# PowCarbinBoard_Connect.net
KiCad netlist of a schematic drawn in Altium Designer
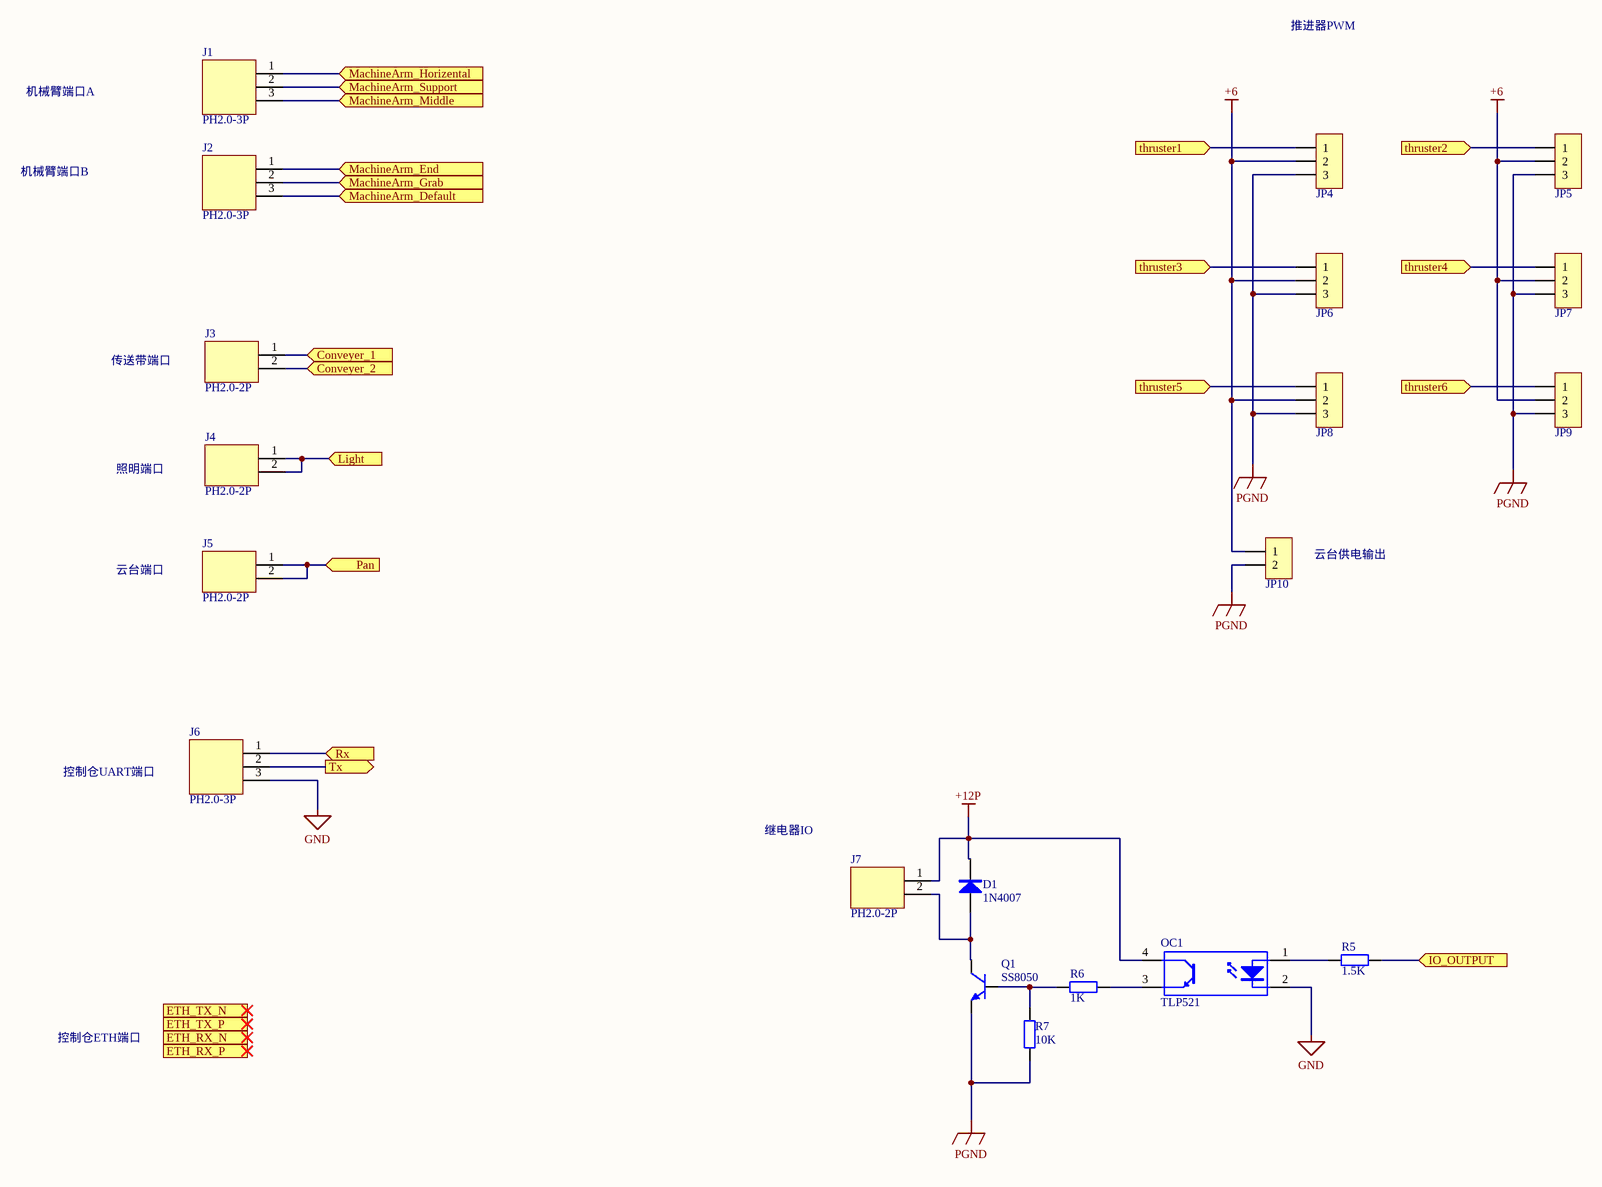
[diagram p0: PowCarbinBoard_Connect.SchDoc]

(export (version "E")
  (design (tool "Eeschema 10.0.6"))
  (components
    (comp (ref "D1")
      (value "1N4007")
      (footprint "SOD-123")
      (description "整流二极管")
      (fields (field (name "版权归属") "源创客"))
      (libsource (lib "8.1   - 二极管-整流桥") (part "1N4007"))
    )
    (comp (ref "J1") (value "PH2.0-3P") (footprint "PH2.0-3P") (libsource (lib "PH") (part "PH2.0-3P")))
    (comp (ref "J2") (value "PH2.0-3P") (footprint "PH2.0-3P") (libsource (lib "PH") (part "PH2.0-3P")))
    (comp (ref "J3") (value "PH2.0-2P") (footprint "PH2.0-2P") (libsource (lib "PH") (part "PH2.0-2P")))
    (comp (ref "J4") (value "PH2.0-2P") (footprint "PH2.0-2P") (libsource (lib "PH") (part "PH2.0-2P")))
    (comp (ref "J5") (value "PH2.0-2P") (footprint "PH2.0-2P") (libsource (lib "PH") (part "PH2.0-2P")))
    (comp (ref "J6") (value "PH2.0-3P") (footprint "PH2.0-3P") (libsource (lib "PH") (part "PH2.0-3P")))
    (comp (ref "J7") (value "PH2.0-2P") (footprint "PH2.0-2P") (libsource (lib "PH") (part "PH2.0-2P")))
    (comp (ref "JP4")
      (value "HDR-1X3")
      (footprint "HDR2.54-LI-3P")
      (description "3P接插件")
      (fields (field (name "版权归属") "源创客"))
      (libsource (lib "4.5   - 接插件-脚距2.54") (part "Header 3"))
    )
    (comp (ref "JP5")
      (value "HDR-1X3")
      (footprint "HDR2.54-LI-3P")
      (description "3P接插件")
      (fields (field (name "版权归属") "源创客"))
      (libsource (lib "4.5   - 接插件-脚距2.54") (part "Header 3"))
    )
    (comp (ref "JP6")
      (value "HDR-1X3")
      (footprint "HDR2.54-LI-3P")
      (description "3P接插件")
      (fields (field (name "版权归属") "源创客"))
      (libsource (lib "4.5   - 接插件-脚距2.54") (part "Header 3"))
    )
    (comp (ref "JP7")
      (value "HDR-1X3")
      (footprint "HDR2.54-LI-3P")
      (description "3P接插件")
      (fields (field (name "版权归属") "源创客"))
      (libsource (lib "4.5   - 接插件-脚距2.54") (part "Header 3"))
    )
    (comp (ref "JP8")
      (value "HDR-1X3")
      (footprint "HDR2.54-LI-3P")
      (description "3P接插件")
      (fields (field (name "版权归属") "源创客"))
      (libsource (lib "4.5   - 接插件-脚距2.54") (part "Header 3"))
    )
    (comp (ref "JP9")
      (value "HDR-1X3")
      (footprint "HDR2.54-LI-3P")
      (description "3P接插件")
      (fields (field (name "版权归属") "源创客"))
      (libsource (lib "4.5   - 接插件-脚距2.54") (part "Header 3"))
    )
    (comp (ref "JP10")
      (value "HDR-1X2")
      (footprint "KF128-5.08-2P")
      (description "2P接插件")
      (fields (field (name "版权归属") "源创客"))
      (libsource (lib "4.10 - 接插件-脚距5.08") (part "Header 2"))
    )
    (comp (ref "OC1")
      (value "TLP521")
      (footprint "DIP_TLP521")
      (description "开关光耦")
      (libsource (lib "光电隔离器") (part "TLP521"))
    )
    (comp (ref "Q1")
      (value "SS8050")
      (footprint "SOT23-3N")
      (description "高频放大-NPN型")
      (fields (field (name "版权归属") "源创客"))
      (libsource (lib "6.2   - 三极管") (part "8050-SMD"))
    )
    (comp (ref "R5")
      (value "1.5K")
      (footprint "0603_R")
      (description "贴片电阻")
      (libsource (lib "") (part "0603 10KΩ (1002) 1%_1"))
    )
    (comp (ref "R6")
      (value "1K")
      (footprint "0603_R")
      (description "贴片电阻")
      (libsource (lib "Miscellaneous Devices LC") (part "0603 10KΩ (1002) 1%"))
    )
    (comp (ref "R7")
      (value "10K")
      (footprint "0603_R")
      (description "贴片电阻")
      (libsource (lib "") (part "0603 10KΩ (1002) 1%_2"))
    )
  )
  (nets
    (net (code "1") (name "+6") (class "Default")
      (node (ref "JP10") (pin "1") (pinfunction "1_1") (pintype "passive"))
      (node (ref "JP4") (pin "2") (pinfunction "2_2") (pintype "passive"))
      (node (ref "JP5") (pin "2") (pinfunction "2_2") (pintype "passive"))
      (node (ref "JP6") (pin "2") (pinfunction "2_2") (pintype "passive"))
      (node (ref "JP7") (pin "2") (pinfunction "2_2") (pintype "passive"))
      (node (ref "JP8") (pin "2") (pinfunction "2_2") (pintype "passive"))
      (node (ref "JP9") (pin "2") (pinfunction "2_2") (pintype "passive"))
    )
    (net (code "2") (name "+12P") (class "Default")
      (node (ref "D1") (pin "2") (pinfunction "K_2") (pintype "passive"))
      (node (ref "J7") (pin "1") (pinfunction "1_1") (pintype "passive"))
      (node (ref "OC1") (pin "4") (pinfunction "C_4") (pintype "passive"))
    )
    (net (code "3") (name "/Conveyer_1") (class "Default")
      (node (ref "J3") (pin "1") (pinfunction "1_1") (pintype "passive"))
    )
    (net (code "4") (name "/Conveyer_2") (class "Default")
      (node (ref "J3") (pin "2") (pinfunction "2_2") (pintype "passive"))
    )
    (net (code "9") (name "/IO_OUTPUT") (class "Default")
      (node (ref "R5") (pin "2") (pinfunction "2_2") (pintype "passive"))
    )
    (net (code "10") (name "/Light") (class "Default")
      (node (ref "J4") (pin "1") (pinfunction "1_1") (pintype "passive"))
      (node (ref "J4") (pin "2") (pinfunction "2_2") (pintype "passive"))
    )
    (net (code "11") (name "/MachineArm_Default") (class "Default")
      (node (ref "J2") (pin "3") (pinfunction "3_3") (pintype "passive"))
    )
    (net (code "12") (name "/MachineArm_End") (class "Default")
      (node (ref "J2") (pin "1") (pinfunction "1_1") (pintype "passive"))
    )
    (net (code "13") (name "/MachineArm_Grab") (class "Default")
      (node (ref "J2") (pin "2") (pinfunction "2_2") (pintype "passive"))
    )
    (net (code "14") (name "/MachineArm_Horizental") (class "Default")
      (node (ref "J1") (pin "1") (pinfunction "1_1") (pintype "passive"))
    )
    (net (code "15") (name "/MachineArm_Middle") (class "Default")
      (node (ref "J1") (pin "3") (pinfunction "3_3") (pintype "passive"))
    )
    (net (code "16") (name "/MachineArm_Support") (class "Default")
      (node (ref "J1") (pin "2") (pinfunction "2_2") (pintype "passive"))
    )
    (net (code "17") (name "/Pan") (class "Default")
      (node (ref "J5") (pin "1") (pinfunction "1_1") (pintype "passive"))
      (node (ref "J5") (pin "2") (pinfunction "2_2") (pintype "passive"))
    )
    (net (code "18") (name "/Rx") (class "Default")
      (node (ref "J6") (pin "1") (pinfunction "1_1") (pintype "passive"))
    )
    (net (code "19") (name "/Tx") (class "Default")
      (node (ref "J6") (pin "2") (pinfunction "2_2") (pintype "passive"))
    )
    (net (code "20") (name "/thruster1") (class "Default")
      (node (ref "JP4") (pin "1") (pinfunction "1_1") (pintype "passive"))
    )
    (net (code "21") (name "/thruster2") (class "Default")
      (node (ref "JP5") (pin "1") (pinfunction "1_1") (pintype "passive"))
    )
    (net (code "22") (name "/thruster3") (class "Default")
      (node (ref "JP6") (pin "1") (pinfunction "1_1") (pintype "passive"))
    )
    (net (code "23") (name "/thruster4") (class "Default")
      (node (ref "JP7") (pin "1") (pinfunction "1_1") (pintype "passive"))
    )
    (net (code "24") (name "/thruster5") (class "Default")
      (node (ref "JP8") (pin "1") (pinfunction "1_1") (pintype "passive"))
    )
    (net (code "25") (name "/thruster6") (class "Default")
      (node (ref "JP9") (pin "1") (pinfunction "1_1") (pintype "passive"))
    )
    (net (code "26") (name "GND") (class "Default")
      (node (ref "J6") (pin "3") (pinfunction "3_3") (pintype "passive"))
      (node (ref "OC1") (pin "2") (pinfunction "K_2") (pintype "passive"))
    )
    (net (code "27") (name "Net-(D1-A)") (class "Default")
      (node (ref "D1") (pin "1") (pinfunction "A_1") (pintype "passive"))
      (node (ref "J7") (pin "2") (pinfunction "2_2") (pintype "passive"))
      (node (ref "Q1") (pin "3") (pinfunction "C_3") (pintype "passive"))
    )
    (net (code "28") (name "Net-(OC1-A)") (class "Default")
      (node (ref "OC1") (pin "1") (pinfunction "A_1") (pintype "passive"))
      (node (ref "R5") (pin "1") (pinfunction "1_1") (pintype "passive"))
    )
    (net (code "29") (name "Net-(OC1-E)") (class "Default")
      (node (ref "OC1") (pin "3") (pinfunction "E_3") (pintype "passive"))
      (node (ref "R6") (pin "1") (pinfunction "1_1") (pintype "passive"))
    )
    (net (code "30") (name "Net-(Q1-B)") (class "Default")
      (node (ref "Q1") (pin "1") (pinfunction "B_1") (pintype "passive"))
      (node (ref "R6") (pin "2") (pinfunction "2_2") (pintype "passive"))
      (node (ref "R7") (pin "2") (pinfunction "2_2") (pintype "passive"))
    )
    (net (code "31") (name "PGND") (class "Default")
      (node (ref "JP10") (pin "2") (pinfunction "2_2") (pintype "passive"))
      (node (ref "JP4") (pin "3") (pinfunction "3_3") (pintype "passive"))
      (node (ref "JP5") (pin "3") (pinfunction "3_3") (pintype "passive"))
      (node (ref "JP6") (pin "3") (pinfunction "3_3") (pintype "passive"))
      (node (ref "JP7") (pin "3") (pinfunction "3_3") (pintype "passive"))
      (node (ref "JP8") (pin "3") (pinfunction "3_3") (pintype "passive"))
      (node (ref "JP9") (pin "3") (pinfunction "3_3") (pintype "passive"))
      (node (ref "Q1") (pin "2") (pinfunction "E_2") (pintype "passive"))
      (node (ref "R7") (pin "1") (pinfunction "1_1") (pintype "passive"))
    )
  )
)
